# blink1mk3_002.net
KiCad netlist of a schematic drawn in EAGLE
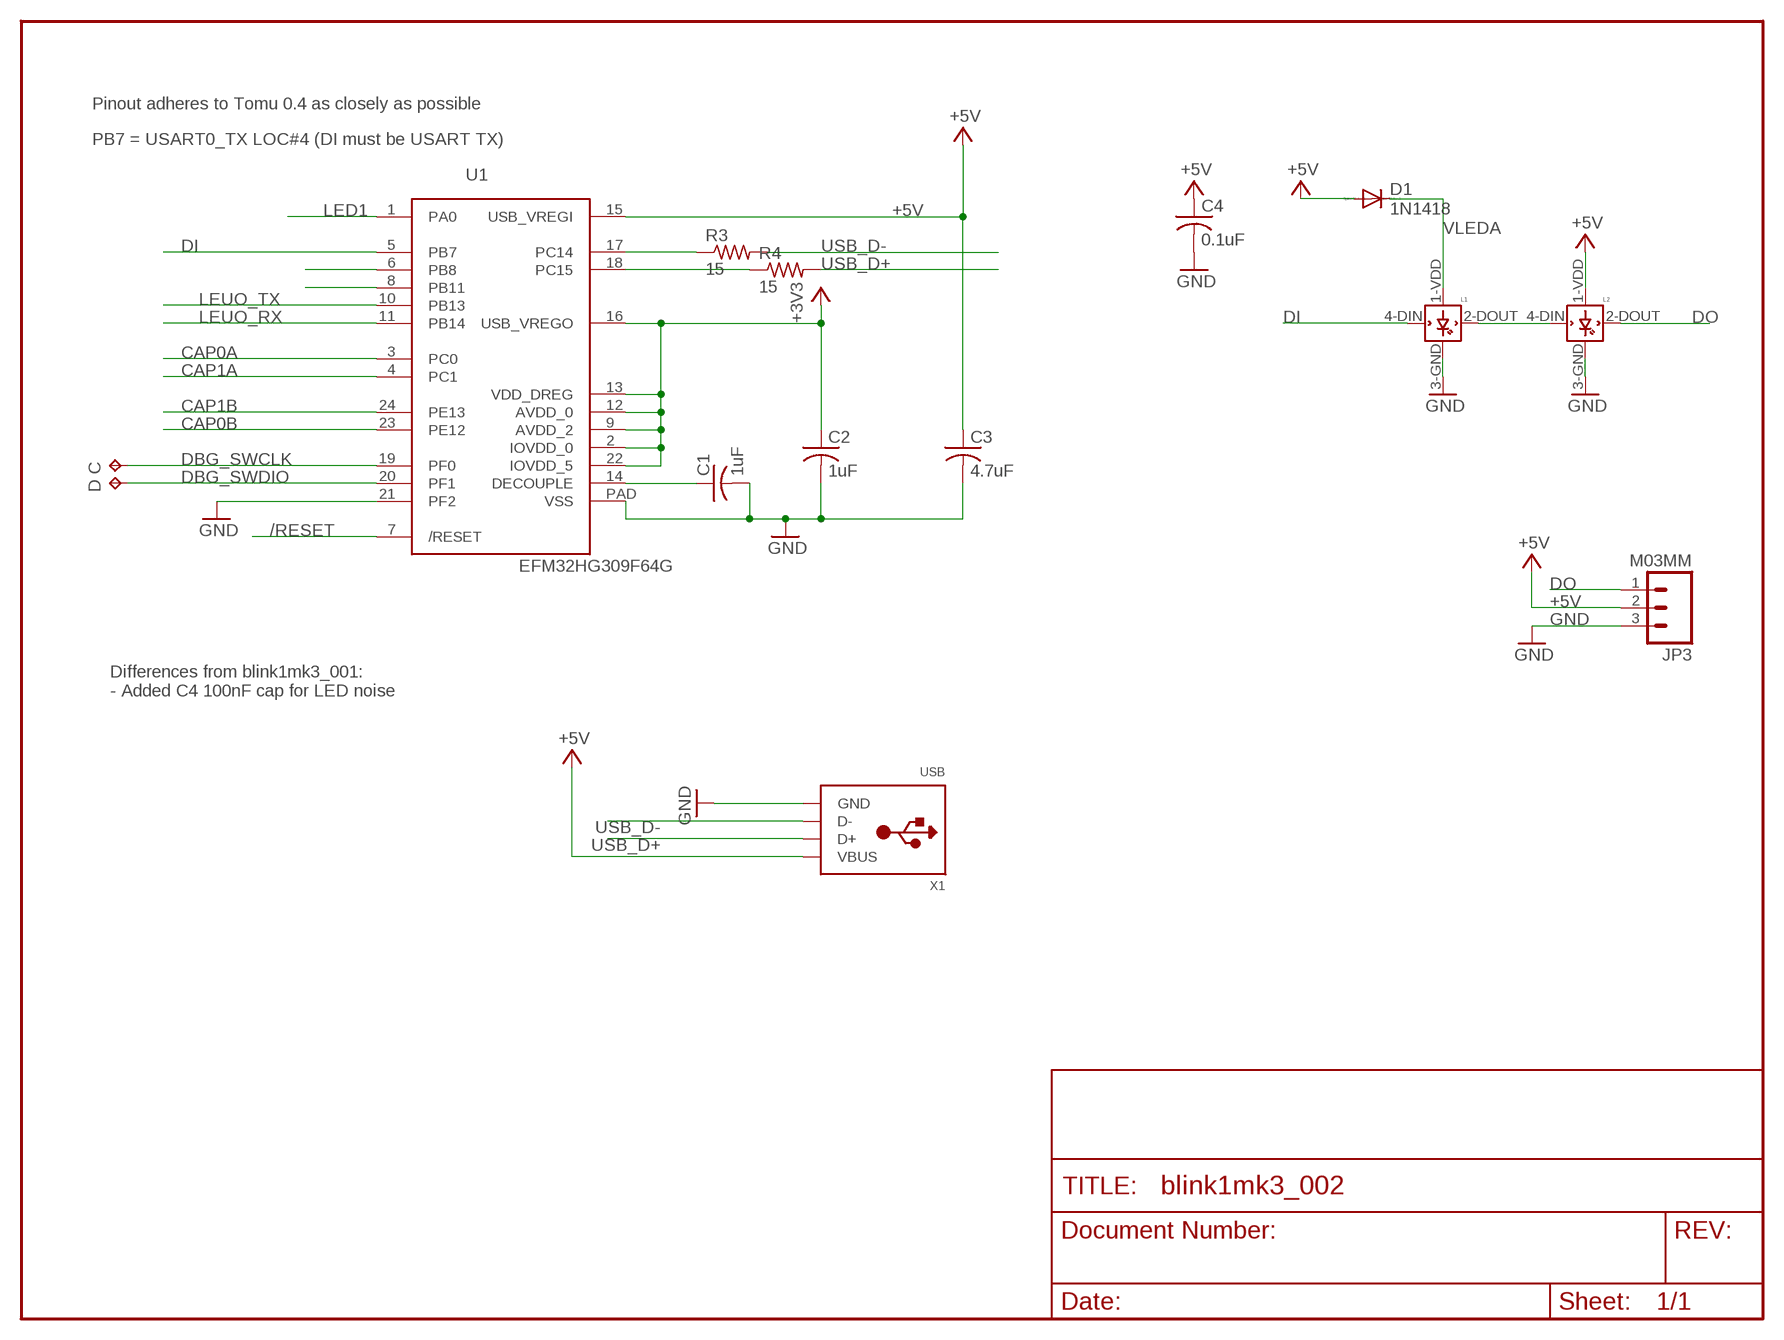
[diagram p0: schematic, sheet 1]

(export (version "E")
  (design (tool "Eeschema 10.0.6"))
  (components
    (comp (ref "C")
      (value "TPTP10R")
      (footprint "eagle-import:TP10R")
      (libsource (lib "eagle-import") (part "TPTP10R"))
    )
    (comp (ref "C1")
      (value "1uF")
      (footprint "eagle-import:C0402")
      (libsource (lib "eagle-import") (part "C-USC0402"))
    )
    (comp (ref "C2")
      (value "1uF")
      (footprint "eagle-import:C0402")
      (libsource (lib "eagle-import") (part "C-USC0402"))
    )
    (comp (ref "C3")
      (value "4.7uF")
      (footprint "eagle-import:C0402")
      (libsource (lib "eagle-import") (part "C-USC0402"))
    )
    (comp (ref "C4")
      (value "0.1uF")
      (footprint "eagle-import:C0402")
      (libsource (lib "eagle-import") (part "C-USC0402"))
    )
    (comp (ref "D")
      (value "TPTP10R")
      (footprint "eagle-import:TP10R")
      (libsource (lib "eagle-import") (part "TPTP10R"))
    )
    (comp (ref "D1")
      (value "1N1418")
      (footprint "eagle-import:SOD523")
      (libsource (lib "eagle-import") (part "DIODE-SOD523"))
    )
    (comp (ref "JP3")
      (value "M03MM")
      (footprint "eagle-import:1X03-1.5MM")
      (libsource (lib "eagle-import") (part "M03MM"))
    )
    (comp (ref "L1")
      (value "WS2812B")
      (footprint "eagle-import:WS2812B")
      (libsource (lib "eagle-import") (part "WS2812B"))
    )
    (comp (ref "L2")
      (value "WS2812B")
      (footprint "eagle-import:WS2812B")
      (libsource (lib "eagle-import") (part "WS2812B"))
    )
    (comp (ref "R3")
      (value "15")
      (footprint "eagle-import:R0402")
      (libsource (lib "eagle-import") (part "R-US_R0402"))
    )
    (comp (ref "R4")
      (value "15")
      (footprint "eagle-import:R0402")
      (libsource (lib "eagle-import") (part "R-US_R0402"))
    )
    (comp (ref "U1")
      (value "EFM32HG309F64G")
      (footprint "eagle-import:QFN24PAD")
      (libsource (lib "eagle-import") (part "EFM32HG309F64G"))
    )
    (comp (ref "X1")
      (value "USB")
      (footprint "eagle-import:MOLEX-48037-1000")
      (libsource (lib "eagle-import") (part "USB"))
    )
  )
  (nets
    (net (code "1") (name "+3V3") (class "Default")
      (node (ref "C2") (pin "1") (pinfunction "1_1") (pintype "passive"))
      (node (ref "U1") (pin "12") (pinfunction "AVDD_0_12") (pintype "bidirectional"))
      (node (ref "U1") (pin "13") (pinfunction "VDD_DREG_13") (pintype "bidirectional"))
      (node (ref "U1") (pin "16") (pinfunction "USB_VREGO_16") (pintype "bidirectional"))
      (node (ref "U1") (pin "2") (pinfunction "IOVDD_0_2") (pintype "bidirectional"))
      (node (ref "U1") (pin "22") (pinfunction "IOVDD_5_22") (pintype "bidirectional"))
      (node (ref "U1") (pin "9") (pinfunction "AVDD_2_9") (pintype "bidirectional"))
    )
    (net (code "2") (name "+5V") (class "Default")
      (node (ref "C3") (pin "1") (pinfunction "1_1") (pintype "passive"))
      (node (ref "C4") (pin "1") (pinfunction "1_1") (pintype "passive"))
      (node (ref "D1") (pin "A") (pinfunction "A_A") (pintype "passive"))
      (node (ref "JP3") (pin "2") (pinfunction "2_2") (pintype "passive"))
      (node (ref "L2") (pin "1-VDD") (pinfunction "VDD_1-VDD") (pintype "bidirectional"))
      (node (ref "U1") (pin "15") (pinfunction "USB_VREGI_15") (pintype "bidirectional"))
      (node (ref "X1") (pin "1") (pinfunction "VBUS_1") (pintype "power_in"))
    )
    (net (code "3") (name "/CAP0A") (class "Default")
      (node (ref "U1") (pin "3") (pinfunction "PC0_3") (pintype "bidirectional"))
    )
    (net (code "4") (name "/CAP0B") (class "Default")
      (node (ref "U1") (pin "23") (pinfunction "PE12_23") (pintype "bidirectional"))
    )
    (net (code "5") (name "/CAP1A") (class "Default")
      (node (ref "U1") (pin "4") (pinfunction "PC1_4") (pintype "bidirectional"))
    )
    (net (code "6") (name "/CAP1B") (class "Default")
      (node (ref "U1") (pin "24") (pinfunction "PE13_24") (pintype "bidirectional"))
    )
    (net (code "7") (name "/DBG_SWCLK") (class "Default")
      (node (ref "C") (pin "TP") (pinfunction "TP_TP") (pintype "input"))
      (node (ref "U1") (pin "19") (pinfunction "PF0_19") (pintype "bidirectional"))
    )
    (net (code "8") (name "/DBG_SWDIO") (class "Default")
      (node (ref "D") (pin "TP") (pinfunction "TP_TP") (pintype "input"))
      (node (ref "U1") (pin "20") (pinfunction "PF1_20") (pintype "bidirectional"))
    )
    (net (code "9") (name "/DI") (class "Default")
      (node (ref "L1") (pin "4-DIN") (pinfunction "DIN_4-DIN") (pintype "input"))
      (node (ref "U1") (pin "5") (pinfunction "PB7_5") (pintype "bidirectional"))
    )
    (net (code "10") (name "/DO") (class "Default")
      (node (ref "JP3") (pin "1") (pinfunction "1_1") (pintype "passive"))
      (node (ref "L2") (pin "2-DOUT") (pinfunction "DOUT_2-DOUT") (pintype "output"))
    )
    (net (code "11") (name "/LED1") (class "Default")
      (node (ref "U1") (pin "1") (pinfunction "PA0_1") (pintype "bidirectional"))
    )
    (net (code "12") (name "/LEUO_RX") (class "Default")
      (node (ref "U1") (pin "11") (pinfunction "PB14_11") (pintype "bidirectional"))
    )
    (net (code "13") (name "/LEUO_TX") (class "Default")
      (node (ref "U1") (pin "10") (pinfunction "PB13_10") (pintype "bidirectional"))
    )
    (net (code "14") (name "/USB_D+") (class "Default")
      (node (ref "R4") (pin "2") (pinfunction "2_2") (pintype "passive"))
      (node (ref "X1") (pin "3") (pinfunction "D+_3") (pintype "bidirectional"))
    )
    (net (code "15") (name "/USB_D-") (class "Default")
      (node (ref "R3") (pin "2") (pinfunction "2_2") (pintype "passive"))
      (node (ref "X1") (pin "2") (pinfunction "D-_2") (pintype "bidirectional"))
    )
    (net (code "16") (name "/VLEDA") (class "Default")
      (node (ref "D1") (pin "C") (pinfunction "C_C") (pintype "passive"))
      (node (ref "L1") (pin "1-VDD") (pinfunction "VDD_1-VDD") (pintype "bidirectional"))
    )
    (net (code "17") (name "/{slash}RESET") (class "Default")
      (node (ref "U1") (pin "7") (pinfunction "/RESET_7") (pintype "bidirectional"))
    )
    (net (code "18") (name "GND") (class "Default")
      (node (ref "C1") (pin "2") (pinfunction "2_2") (pintype "passive"))
      (node (ref "C2") (pin "2") (pinfunction "2_2") (pintype "passive"))
      (node (ref "C3") (pin "2") (pinfunction "2_2") (pintype "passive"))
      (node (ref "C4") (pin "2") (pinfunction "2_2") (pintype "passive"))
      (node (ref "JP3") (pin "3") (pinfunction "3_3") (pintype "passive"))
      (node (ref "L1") (pin "3-GND") (pinfunction "GND_3-GND") (pintype "bidirectional"))
      (node (ref "L2") (pin "3-GND") (pinfunction "GND_3-GND") (pintype "bidirectional"))
      (node (ref "U1") (pin "21") (pinfunction "PF2_21") (pintype "bidirectional"))
      (node (ref "U1") (pin "PAD") (pinfunction "VSS_PAD") (pintype "bidirectional"))
      (node (ref "X1") (pin "4") (pinfunction "GND_4") (pintype "power_in"))
    )
    (net (code "19") (name "Net-(L1-DOUT)") (class "Default")
      (node (ref "L1") (pin "2-DOUT") (pinfunction "DOUT_2-DOUT") (pintype "output"))
      (node (ref "L2") (pin "4-DIN") (pinfunction "DIN_4-DIN") (pintype "input"))
    )
    (net (code "20") (name "Net-(U1-DECOUPLE)") (class "Default")
      (node (ref "C1") (pin "1") (pinfunction "1_1") (pintype "passive"))
      (node (ref "U1") (pin "14") (pinfunction "DECOUPLE_14") (pintype "bidirectional"))
    )
    (net (code "21") (name "Net-(U1-PC14)") (class "Default")
      (node (ref "R3") (pin "1") (pinfunction "1_1") (pintype "passive"))
      (node (ref "U1") (pin "17") (pinfunction "PC14_17") (pintype "bidirectional"))
    )
    (net (code "22") (name "Net-(U1-PC15)") (class "Default")
      (node (ref "R4") (pin "1") (pinfunction "1_1") (pintype "passive"))
      (node (ref "U1") (pin "18") (pinfunction "PC15_18") (pintype "bidirectional"))
    )
    (net (code "23") (name "unconnected-(U1-PB8-Pad6)") (class "Default")
      (node (ref "U1") (pin "6") (pinfunction "PB8_6") (pintype "bidirectional"))
    )
    (net (code "24") (name "unconnected-(U1-PB11-Pad8)") (class "Default")
      (node (ref "U1") (pin "8") (pinfunction "PB11_8") (pintype "bidirectional"))
    )
  )
)
